# CAN.net
KiCad netlist of a schematic drawn in Altium Designer
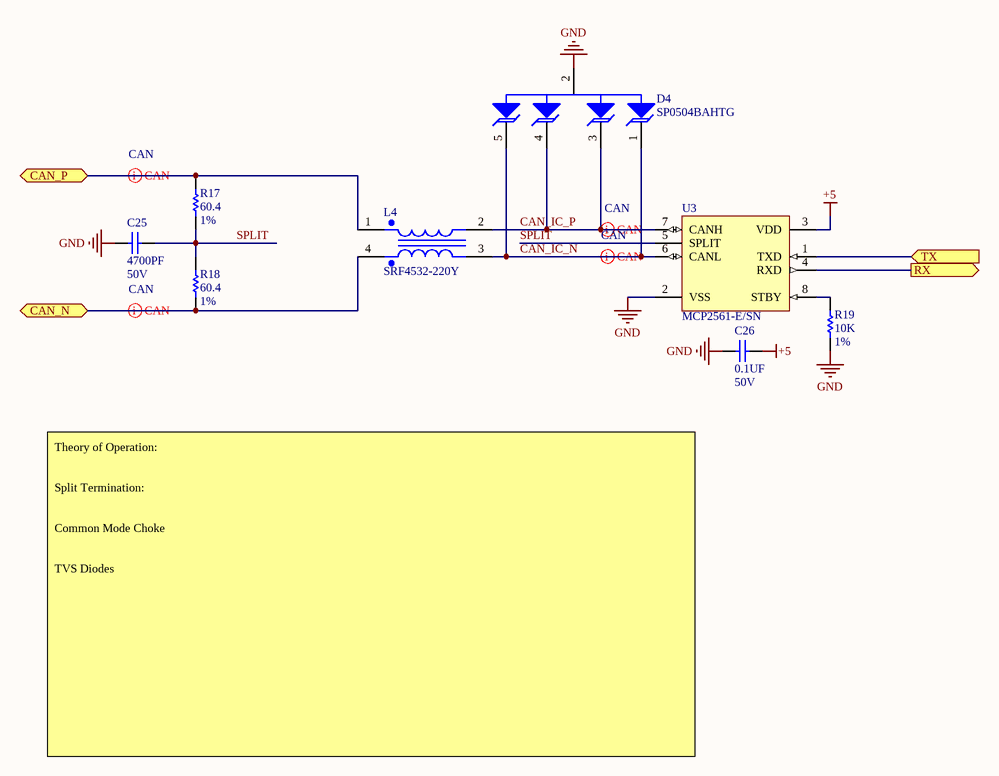
[diagram p0: CAN.SchDoc]

(export (version "E")
  (design (tool "Eeschema 10.0.6"))
  (components
    (comp (ref "C25")
      (value "CAP 0603 4700PF 50V 10% X7R")
      (footprint "0603_CAP")
      (description "Capacitor Surface Mount 0603 Footprint 4700PF 50V 10% Tolerance Ceramic X7R")
      (fields
        (field (name "VAL") "4700PF")
        (field (name "VOL") "50V")
        (field (name "MANUFACTURER") "Various")
        (field (name "VOLTAGE") "50V")
      )
      (libsource (lib "Passive Components") (part "cap"))
    )
    (comp (ref "C26")
      (value "CAP 0603 0.1UF 50V 10% X7R")
      (footprint "0603_CAP")
      (description "Capacitor Surface Mount 0603 Footprint 0.1UF 50V 10% Tolerance Ceramic X7R")
      (fields
        (field (name "VAL") "0.1UF")
        (field (name "VOL") "50V")
        (field (name "MANUFACTURER") "Various")
        (field (name "VOLTAGE") "50V")
      )
      (libsource (lib "Passive Components") (part "cap"))
    )
    (comp (ref "D4")
      (value "SP0504BAHTG")
      (footprint "SOT23127P600-8N")
      (description "8.5V Clamp  Ipp Tvs Diode Surface Mount SOT-23-5 5.5V")
      (fields (field (name "MANUFACTURER") "Littelfuse"))
      (libsource (lib "AERO Parts") (part "SP0504BAHTG"))
    )
    (comp (ref "L4")
      (value "SRF4532-220Y")
      (footprint "IND_BOURNS_SRF45")
      (description "22µH @ 100kHz 2 Line Common Mode Choke Surface Mount 1 kOhms @ 10MHz 200mA DCR 2.65Ohm")
      (fields (field (name "MANUFACTURER") "Bourns") (field (name "TOLERANCE") "50%"))
      (libsource (lib "AERO Parts") (part "SRF4532-220Y"))
    )
    (comp (ref "R17")
      (value "RES 0805 60.4 1%")
      (footprint "0805_RES")
      (description "Resistor Surface Mount, 60.4 Ohms, 0805 Footprint, 1% Tolerance 0.125W")
      (fields
        (field (name "VAL") "60.4")
        (field (name "TOL") "1%")
        (field (name "MANUFACTURER") "Various")
        (field (name "TOLERANCE") "1%")
      )
      (libsource (lib "Passive Components") (part "res"))
    )
    (comp (ref "R18")
      (value "RES 0805 60.4 1%")
      (footprint "0805_RES")
      (description "Resistor Surface Mount, 60.4 Ohms, 0805 Footprint, 1% Tolerance 0.125W")
      (fields
        (field (name "VAL") "60.4")
        (field (name "TOL") "1%")
        (field (name "MANUFACTURER") "Various")
        (field (name "TOLERANCE") "1%")
      )
      (libsource (lib "Passive Components") (part "res"))
    )
    (comp (ref "R19")
      (value "RES 0603 10K 1%")
      (footprint "0603_RES")
      (description "Resistor Surface Mount, 10K Ohms, 0603 Footprint, 1% Tolerance 0.1W")
      (fields
        (field (name "VAL") "10K")
        (field (name "TOL") "1%")
        (field (name "MANUFACTURER") "Various")
        (field (name "TOLERANCE") "1%")
      )
      (libsource (lib "Passive Components") (part "res"))
    )
    (comp (ref "U3")
      (value "MCP2561-E/SN")
      (footprint "Microchip_C04-2057A_0")
      (description "1/1 Transceiver CANbus 8-SOIC")
      (fields
        (field (name "VOLTAGE") "4.5V ~ 5.5V")
        (field (name "MANUFACTURER") "Microchip")
        (field (name "PART NUMBER") "MCP2561-E/SN")
      )
      (libsource (lib "AERO Parts") (part "MCP2561-E/SN"))
    )
  )
  (nets
    (net (code "1") (name "+5") (class "Default")
      (node (ref "C26") (pin "2") (pinfunction "2_2") (pintype "passive"))
      (node (ref "U3") (pin "3") (pinfunction "VDD_3") (pintype "power_in"))
    )
    (net (code "2") (name "/CAN_IC_N") (class "Default")
      (node (ref "D4") (pin "1") (pinfunction "1_1") (pintype "passive"))
      (node (ref "D4") (pin "5") (pinfunction "5_5") (pintype "passive"))
      (node (ref "L4") (pin "3") (pinfunction "3_3") (pintype "passive"))
      (node (ref "U3") (pin "6") (pinfunction "CANL_6") (pintype "bidirectional"))
    )
    (net (code "3") (name "/CAN_IC_P") (class "Default")
      (node (ref "D4") (pin "3") (pinfunction "3_3") (pintype "passive"))
      (node (ref "D4") (pin "4") (pinfunction "4_4") (pintype "passive"))
      (node (ref "L4") (pin "2") (pinfunction "2_2") (pintype "passive"))
      (node (ref "U3") (pin "7") (pinfunction "CANH_7") (pintype "bidirectional"))
    )
    (net (code "4") (name "/CAN_N") (class "Default")
      (node (ref "L4") (pin "4") (pinfunction "4_4") (pintype "passive"))
      (node (ref "R18") (pin "1") (pinfunction "1_1") (pintype "passive"))
    )
    (net (code "5") (name "/CAN_P") (class "Default")
      (node (ref "L4") (pin "1") (pinfunction "1_1") (pintype "passive"))
      (node (ref "R17") (pin "2") (pinfunction "2_2") (pintype "passive"))
    )
    (net (code "6") (name "/RX") (class "Default")
      (node (ref "U3") (pin "4") (pinfunction "RXD_4") (pintype "output"))
    )
    (net (code "7") (name "/SPLIT") (class "Default")
      (node (ref "C25") (pin "2") (pinfunction "2_2") (pintype "passive"))
      (node (ref "R17") (pin "1") (pinfunction "1_1") (pintype "passive"))
      (node (ref "R18") (pin "2") (pinfunction "2_2") (pintype "passive"))
      (node (ref "U3") (pin "5") (pinfunction "SPLIT_5") (pintype "passive"))
    )
    (net (code "8") (name "/TX") (class "Default")
      (node (ref "U3") (pin "1") (pinfunction "TXD_1") (pintype "input"))
    )
    (net (code "9") (name "GND") (class "Default")
      (node (ref "C25") (pin "1") (pinfunction "1_1") (pintype "passive"))
      (node (ref "C26") (pin "1") (pinfunction "1_1") (pintype "passive"))
      (node (ref "D4") (pin "2") (pinfunction "2_2") (pintype "passive"))
      (node (ref "R19") (pin "1") (pinfunction "1_1") (pintype "passive"))
      (node (ref "U3") (pin "2") (pinfunction "VSS_2") (pintype "power_in"))
    )
    (net (code "10") (name "Net-(U3-STBY)") (class "Default")
      (node (ref "R19") (pin "2") (pinfunction "2_2") (pintype "passive"))
      (node (ref "U3") (pin "8") (pinfunction "STBY_8") (pintype "input"))
    )
  )
)
